# 03_Power.net
KiCad netlist of a schematic drawn in Altium Designer
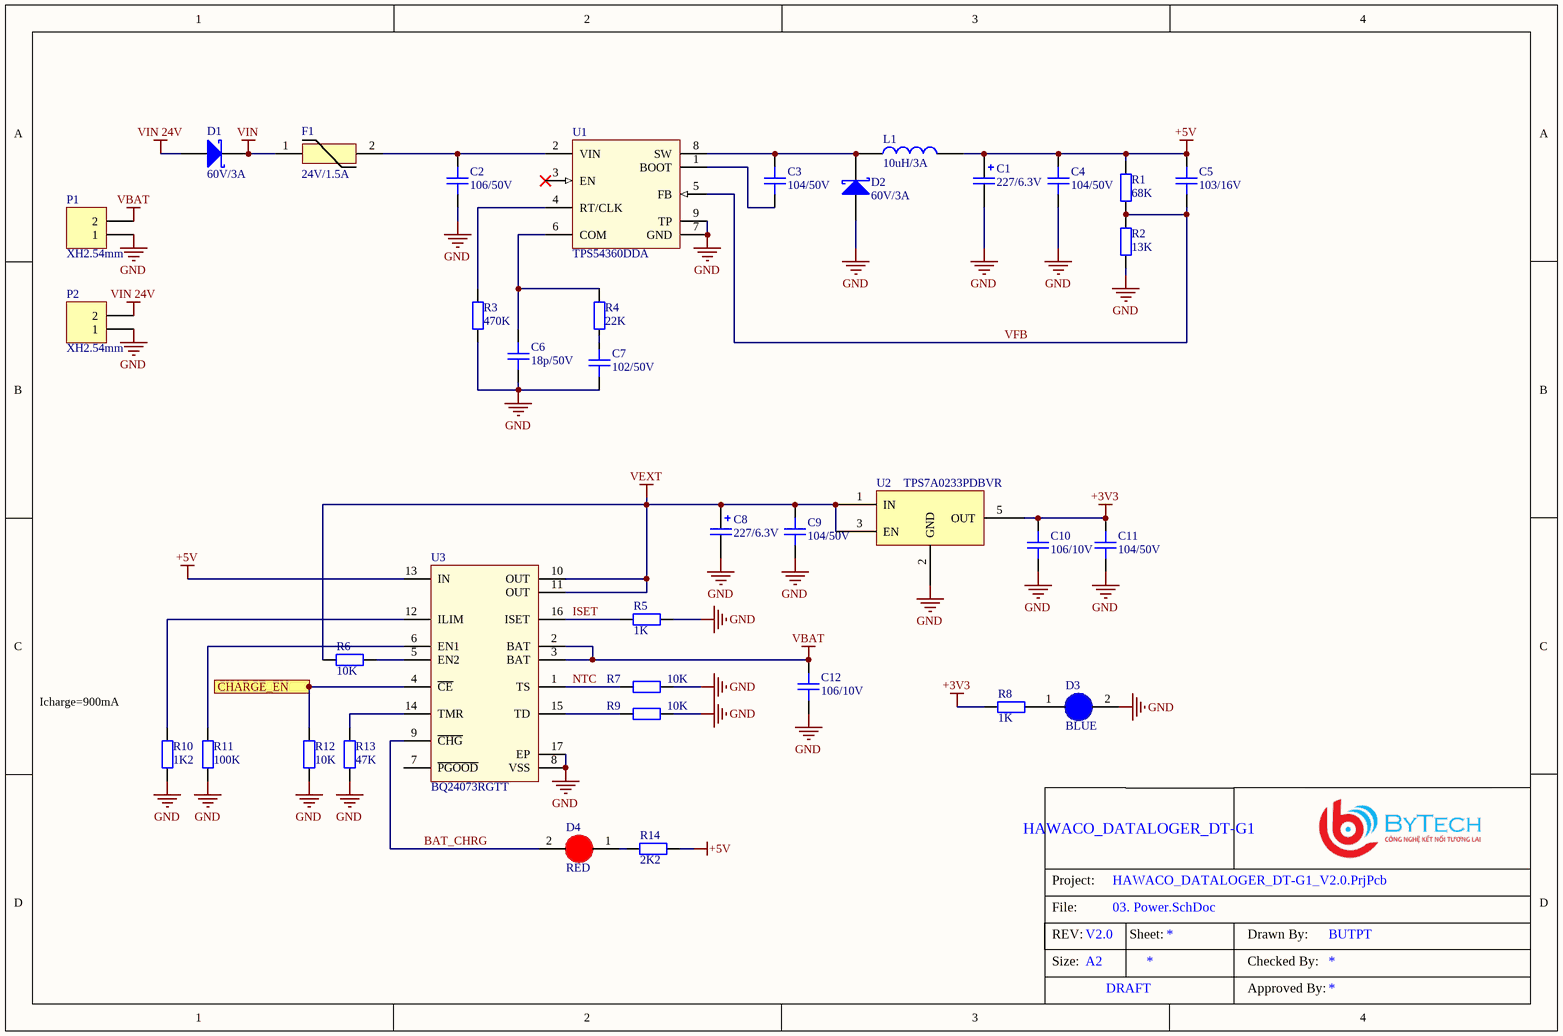
[diagram p0: 03. Power.SchDoc]

(export (version "E")
  (design (tool "Eeschema 10.0.6"))
  (components
    (comp (ref "C1")
      (value "227/6.3V")
      (footprint "CAP_TANTAL_1210(3528)")
      (description "CAP TANT POLY 220uF 20% 6.3V 3528 35mOhm ESR")
      (fields (field (name "MPN") "T520B227M006ATE035"))
      (libsource (lib "01.Passives") (part "T520B227M006ATE035"))
    )
    (comp (ref "C2")
      (value "106/50V")
      (footprint "CAPC-1210 (3225)")
      (description "CAP CER 10uF 10% 50V X7R 1210 (3255)")
      (fields (field (name "MPN") "GRM32ER71H106KA12L"))
      (libsource (lib "01.Passives") (part "GRM32ER71H106KA12L"))
    )
    (comp (ref "C3")
      (value "104/50V")
      (footprint "CAPC-0603 (1608)")
      (description "CAP CER 0.1uF 50V 10% X7R 0603")
      (fields (field (name "MPN") "C0603C104K5RACTU"))
      (libsource (lib "01.Passives") (part "C0603C104K5RACTU"))
    )
    (comp (ref "C4")
      (value "104/50V")
      (footprint "CAPC-0603 (1608)")
      (description "CAP CER 0.1uF 50V 10% X7R 0603")
      (fields (field (name "MPN") "C0603C104K5RACTU"))
      (libsource (lib "01.Passives") (part "C0603C104K5RACTU"))
    )
    (comp (ref "C5")
      (value "103/16V")
      (footprint "CAPC-0603 (1608)")
      (description "CAP CER 10nF 16V 10% X7R 0603")
      (fields (field (name "MPN") "CC0603KRX7R7BB103"))
      (libsource (lib "01.Passives") (part "CC0603KRX7R7BB103"))
    )
    (comp (ref "C6")
      (value "18p/50V")
      (footprint "CAPC-0603 (1608)")
      (description "CAP CER 18pF 5% 50V C0G/NP0 0603")
      (fields (field (name "MPN") "CL10C180JB8NNNC"))
      (libsource (lib "01.Passives") (part "CL10C180JB8NNNC"))
    )
    (comp (ref "C7")
      (value "102/50V")
      (footprint "CAPC-0603 (1608)")
      (description "CAP CER 1nF 50V 10% X7R 0603")
      (fields (field (name "MPN") "C0603C102K5RACTU"))
      (libsource (lib "01.Passives") (part "C0603C102K5RACTU"))
    )
    (comp (ref "C8")
      (value "227/6.3V")
      (footprint "CAP_TANTAL_1210(3528)")
      (description "CAP TANT POLY 220uF 20% 6.3V 3528 35mOhm ESR")
      (fields (field (name "MPN") "T520B227M006ATE035"))
      (libsource (lib "01.Passives") (part "T520B227M006ATE035"))
    )
    (comp (ref "C9")
      (value "104/50V")
      (footprint "CAPC-0603 (1608)")
      (description "CAP CER 0.1uF 50V 10% X7R 0603")
      (fields (field (name "MPN") "C0603C104K5RACTU"))
      (libsource (lib "01.Passives") (part "C0603C104K5RACTU"))
    )
    (comp (ref "C10")
      (value "106/10V")
      (footprint "CAPC-0603 (1608)")
      (description "CAP CER 10uF 10% 10V X5R 0603")
      (fields (field (name "MPN") "CL10A106KP8NNNC"))
      (libsource (lib "01.Passives") (part "CL10A106KP8NNNC"))
    )
    (comp (ref "C11")
      (value "104/50V")
      (footprint "CAPC-0603 (1608)")
      (description "CAP CER 0.1uF 50V 10% X7R 0603")
      (fields (field (name "MPN") "C0603C104K5RACTU"))
      (libsource (lib "01.Passives") (part "C0603C104K5RACTU"))
    )
    (comp (ref "C12")
      (value "106/10V")
      (footprint "CAPC-0603 (1608)")
      (description "CAP CER 10uF 10% 10V X5R 0603")
      (fields (field (name "MPN") "CL10A106KP8NNNC"))
      (libsource (lib "01.Passives") (part "CL10A106KP8NNNC"))
    )
    (comp (ref "D1")
      (value "60V/3A")
      (footprint "DIODE_DO214AC_SMA")
      (description "DIODE SCHOTTKY 60V 3A DO214AC")
      (fields (field (name "MPN") "SK36A-LTP"))
      (libsource (lib "03.Semiconductor") (part "SK36A-LTP"))
    )
    (comp (ref "D2")
      (value "60V/3A")
      (footprint "DIODE_DO214AC_SMA")
      (description "DIODE SCHOTTKY 60V 3A DO214AC")
      (fields (field (name "MPN") "SK36A-LTP") (field (name "MANUFACTURER") "Micro Commercial Co"))
      (libsource (lib "03.Semiconductor") (part "SK36A-LTP"))
    )
    (comp (ref "D3")
      (value "BLUE")
      (footprint "LED 0603")
      (description "LED 0603 BLUE")
      (libsource (lib "03.Semiconductor") (part "LED 0603 BLUE"))
    )
    (comp (ref "D4")
      (value "RED")
      (footprint "LED 0603")
      (description "LED 0603 RED")
      (libsource (lib "03.Semiconductor") (part "LED 0603 RED"))
    )
    (comp (ref "F1")
      (value "24V/1.5A")
      (footprint "FUSE_1812(4532)")
      (description "FUSE PTC RESETTABLE 24V 1.50A 1812L")
      (fields (field (name "MPN") "1812L150/24MR"))
      (libsource (lib "02.Power,Protection") (part "1812L150/24MR"))
    )
    (comp (ref "L1")
      (value "10uH/3A")
      (footprint "IND-IHLP2525-6.86X6.47MM")
      (description "IND-FIXED 10uH 3A 105 mOhm SMD")
      (fields (field (name "MPN") "IHLP2525CZER100M01"))
      (libsource (lib "01.Passives") (part "IHLP2525CZER100M01"))
    )
    (comp (ref "P1")
      (value "XH2.54mm")
      (footprint "XH2.54-2P")
      (description "XH2.54mmm - 2P 180 degree")
      (fields (field (name "MPN") "XH-2A"))
      (libsource (lib "04.Header-Connecter") (part "XH-2A"))
    )
    (comp (ref "P2")
      (value "XH2.54mm")
      (footprint "XH2.54-2P")
      (description "XH2.54mmm - 2P 180 degree")
      (fields (field (name "MPN") "XH-2A"))
      (libsource (lib "04.Header-Connecter") (part "XH-2A"))
    )
    (comp (ref "R1")
      (value "68K")
      (footprint "RESC-0603 (1608)")
      (description "RES SMD 68K OHM 1% 1/10W 0603")
      (fields (field (name "MPN") "CRCW060368K0FKEA"))
      (libsource (lib "01.Passives") (part "CRCW060368K0FKEA"))
    )
    (comp (ref "R2")
      (value "13K")
      (footprint "RESC-0603 (1608)")
      (description "RES SMD 13K OHM 1% 1/10W 0603")
      (fields (field (name "MPN") "AC0603FR-0713KL"))
      (libsource (lib "01.Passives") (part "AC0603FR-0713KL"))
    )
    (comp (ref "R3")
      (value "470K")
      (footprint "RESC-0603 (1608)")
      (description "RES SMD 470K OHM 1% 1/10W 0603")
      (fields (field (name "MPN") "RC0603FR-07470K"))
      (libsource (lib "01.Passives") (part "RC0603FR-07470KL"))
    )
    (comp (ref "R4")
      (value "22K")
      (footprint "RESC-0603 (1608)")
      (description "RES SMD 22K OHM 1% 1/10W 0603")
      (fields (field (name "MPN") "RC0603FR-0722KL"))
      (libsource (lib "01.Passives") (part "RC0603FR-0722KL"))
    )
    (comp (ref "R5")
      (value "1K")
      (footprint "RESC-0603 (1608)")
      (description "RES SMD 1 KOHM 1% 1/10W 0603")
      (fields (field (name "MPN") "RC0603FR-071KL"))
      (libsource (lib "01.Passives") (part "RC0603FR-071KL"))
    )
    (comp (ref "R6")
      (value "10K")
      (footprint "RESC-0603 (1608)")
      (description "RES SMD 10K OHM 1% 1/10W 0603")
      (fields (field (name "MPN") "RC0603FR-0710KL"))
      (libsource (lib "01.Passives") (part "RC0603FR-0710KL"))
    )
    (comp (ref "R7")
      (value "10K")
      (footprint "RESC-0603 (1608)")
      (description "RES SMD 10K OHM 1% 1/10W 0603")
      (fields (field (name "MPN") "RC0603FR-0710KL"))
      (libsource (lib "01.Passives") (part "RC0603FR-0710KL"))
    )
    (comp (ref "R8")
      (value "1K")
      (footprint "RESC-0603 (1608)")
      (description "RES SMD 1 KOHM 1% 1/10W 0603")
      (fields (field (name "MPN") "RC0603FR-071KL"))
      (libsource (lib "01.Passives") (part "RC0603FR-071KL"))
    )
    (comp (ref "R9")
      (value "10K")
      (footprint "RESC-0603 (1608)")
      (description "RES SMD 10K OHM 1% 1/10W 0603")
      (fields (field (name "MPN") "RC0603FR-0710KL"))
      (libsource (lib "01.Passives") (part "RC0603FR-0710KL"))
    )
    (comp (ref "R10")
      (value "1K2")
      (footprint "RESC-0603 (1608)")
      (description "RES SMD 1.2K OHM 1% 1/10W 0603")
      (fields (field (name "MPN") "RC0603FR-071K2L"))
      (libsource (lib "01.Passives") (part "RC0603FR-071K2L"))
    )
    (comp (ref "R11")
      (value "100K")
      (footprint "RESC-0603 (1608)")
      (description "RES SMD 100K OHM 1% 1/10W 0603")
      (fields (field (name "MPN") "RC0603FR-07100KL"))
      (libsource (lib "01.Passives") (part "RC0603FR-07100KL"))
    )
    (comp (ref "R12")
      (value "10K")
      (footprint "RESC-0603 (1608)")
      (description "RES SMD 10K OHM 1% 1/10W 0603")
      (fields (field (name "MPN") "RC0603FR-0710KL"))
      (libsource (lib "") (part "RC0603FR-0710KL_1"))
    )
    (comp (ref "R13")
      (value "47K")
      (footprint "RESC-0603 (1608)")
      (description "RES SMD 47K OHM 1% 1/10W 0603")
      (fields (field (name "MPN") "RC0603FR0747KL"))
      (libsource (lib "01.Passives") (part "RC0603FR0747KL"))
    )
    (comp (ref "R14")
      (value "2K2")
      (footprint "RESC-0603 (1608)")
      (description "RES SMD 2.2K OHM 1% 1/10W 0603")
      (fields (field (name "MPN") "CRCW06032K20FKEA"))
      (libsource (lib "01.Passives") (part "CRCW06032K20FKEA"))
    )
    (comp (ref "U1")
      (value "TPS54360DDA")
      (footprint "DDA8_3P1X2P4")
      (description "IC REG BCK SPLIT RAIL ADJ 8SOPWR")
      (fields (field (name "MANUFACTURER") "Texas Instruments"))
      (libsource (lib "05.IC") (part "TPS54360DDA"))
    )
    (comp (ref "U2")
      (value "TPS7A0233PDBVR")
      (footprint "SOT23-5")
      (description "NANOPOWER LDO")
      (libsource (lib "05.IC") (part "TPS7A0233PDBVR"))
    )
    (comp (ref "U3")
      (value "BQ24073RGTT")
      (footprint "RGT16-1700X1700TP")
      (description "IC LI-ION CHARGE/PWR MGMT 16-QFN")
      (fields (field (name "MFR") "Texas Instruments"))
      (libsource (lib "05.IC") (part "BQ24073RGTT"))
    )
  )
  (nets
    (net (code "1") (name "+3V3") (class "Default")
      (node (ref "C10") (pin "2") (pinfunction "2_2") (pintype "passive"))
      (node (ref "C11") (pin "2") (pinfunction "2_2") (pintype "passive"))
      (node (ref "R8") (pin "1") (pinfunction "1_1") (pintype "passive"))
      (node (ref "U2") (pin "5") (pinfunction "OUT_5") (pintype "passive"))
    )
    (net (code "2") (name "+5V") (class "Default")
      (node (ref "C1") (pin "1") (pinfunction "1_1") (pintype "passive"))
      (node (ref "C4") (pin "2") (pinfunction "2_2") (pintype "passive"))
      (node (ref "C5") (pin "2") (pinfunction "2_2") (pintype "passive"))
      (node (ref "L1") (pin "2") (pinfunction "2_2") (pintype "passive"))
      (node (ref "R1") (pin "2") (pinfunction "2_2") (pintype "passive"))
      (node (ref "R14") (pin "2") (pinfunction "2_2") (pintype "passive"))
      (node (ref "U3") (pin "13") (pinfunction "IN_13") (pintype "power_in"))
    )
    (net (code "3") (name "/BAT_CHRG") (class "Default")
      (node (ref "D4") (pin "2") (pinfunction "K_2") (pintype "passive"))
      (node (ref "U3") (pin "9") (pinfunction "~{CHG}_9") (pintype "power_in"))
    )
    (net (code "4") (name "/CHARGE_EN") (class "Default")
      (node (ref "R12") (pin "2") (pinfunction "2_2") (pintype "passive"))
      (node (ref "U3") (pin "4") (pinfunction "~{CE}_4") (pintype "passive"))
    )
    (net (code "5") (name "/ISET") (class "Default")
      (node (ref "R5") (pin "1") (pinfunction "1_1") (pintype "passive"))
      (node (ref "U3") (pin "16") (pinfunction "ISET_16") (pintype "power_in"))
    )
    (net (code "6") (name "/NTC") (class "Default")
      (node (ref "R7") (pin "1") (pinfunction "1_1") (pintype "passive"))
      (node (ref "U3") (pin "1") (pinfunction "TS_1") (pintype "power_in"))
    )
    (net (code "7") (name "/VFB") (class "Default")
      (node (ref "C5") (pin "1") (pinfunction "1_1") (pintype "passive"))
      (node (ref "R1") (pin "1") (pinfunction "1_1") (pintype "passive"))
      (node (ref "R2") (pin "2") (pinfunction "2_2") (pintype "passive"))
      (node (ref "U1") (pin "5") (pinfunction "FB_5") (pintype "input"))
    )
    (net (code "8") (name "GND") (class "Default")
      (node (ref "C1") (pin "2") (pinfunction "2_2") (pintype "passive"))
      (node (ref "C10") (pin "1") (pinfunction "1_1") (pintype "passive"))
      (node (ref "C11") (pin "1") (pinfunction "1_1") (pintype "passive"))
      (node (ref "C12") (pin "1") (pinfunction "1_1") (pintype "passive"))
      (node (ref "C2") (pin "1") (pinfunction "1_1") (pintype "passive"))
      (node (ref "C4") (pin "1") (pinfunction "1_1") (pintype "passive"))
      (node (ref "C6") (pin "1") (pinfunction "1_1") (pintype "passive"))
      (node (ref "C7") (pin "1") (pinfunction "1_1") (pintype "passive"))
      (node (ref "C8") (pin "2") (pinfunction "2_2") (pintype "passive"))
      (node (ref "C9") (pin "1") (pinfunction "1_1") (pintype "passive"))
      (node (ref "D2") (pin "1") (pinfunction "A_1") (pintype "passive"))
      (node (ref "D3") (pin "2") (pinfunction "K_2") (pintype "passive"))
      (node (ref "P1") (pin "1") (pinfunction "1_1") (pintype "passive"))
      (node (ref "P2") (pin "1") (pinfunction "1_1") (pintype "passive"))
      (node (ref "R10") (pin "1") (pinfunction "1_1") (pintype "passive"))
      (node (ref "R11") (pin "1") (pinfunction "1_1") (pintype "passive"))
      (node (ref "R12") (pin "1") (pinfunction "1_1") (pintype "passive"))
      (node (ref "R13") (pin "1") (pinfunction "1_1") (pintype "passive"))
      (node (ref "R2") (pin "1") (pinfunction "1_1") (pintype "passive"))
      (node (ref "R3") (pin "1") (pinfunction "1_1") (pintype "passive"))
      (node (ref "R5") (pin "2") (pinfunction "2_2") (pintype "passive"))
      (node (ref "R7") (pin "2") (pinfunction "2_2") (pintype "passive"))
      (node (ref "R9") (pin "2") (pinfunction "2_2") (pintype "passive"))
      (node (ref "U1") (pin "7") (pinfunction "GND_7") (pintype "passive"))
      (node (ref "U1") (pin "9") (pinfunction "TP_9") (pintype "passive"))
      (node (ref "U2") (pin "2") (pinfunction "GND_2") (pintype "passive"))
      (node (ref "U3") (pin "17") (pinfunction "EP_17") (pintype "power_in"))
      (node (ref "U3") (pin "8") (pinfunction "VSS_8") (pintype "power_in"))
    )
    (net (code "9") (name "Net-(C7-Pad2)") (class "Default")
      (node (ref "C7") (pin "2") (pinfunction "2_2") (pintype "passive"))
      (node (ref "R4") (pin "1") (pinfunction "1_1") (pintype "passive"))
    )
    (net (code "10") (name "Net-(D2-K)") (class "Default")
      (node (ref "C3") (pin "1") (pinfunction "1_1") (pintype "passive"))
      (node (ref "D2") (pin "2") (pinfunction "K_2") (pintype "passive"))
      (node (ref "L1") (pin "1") (pinfunction "1_1") (pintype "passive"))
      (node (ref "U1") (pin "8") (pinfunction "SW_8") (pintype "passive"))
    )
    (net (code "11") (name "Net-(D3-A)") (class "Default")
      (node (ref "D3") (pin "1") (pinfunction "A_1") (pintype "passive"))
      (node (ref "R8") (pin "2") (pinfunction "2_2") (pintype "passive"))
    )
    (net (code "12") (name "Net-(D4-A)") (class "Default")
      (node (ref "D4") (pin "1") (pinfunction "A_1") (pintype "passive"))
      (node (ref "R14") (pin "1") (pinfunction "1_1") (pintype "passive"))
    )
    (net (code "13") (name "Net-(U1-BOOT)") (class "Default")
      (node (ref "C3") (pin "2") (pinfunction "2_2") (pintype "passive"))
      (node (ref "U1") (pin "1") (pinfunction "BOOT_1") (pintype "passive"))
    )
    (net (code "14") (name "Net-(U1-COM)") (class "Default")
      (node (ref "C6") (pin "2") (pinfunction "2_2") (pintype "passive"))
      (node (ref "R4") (pin "2") (pinfunction "2_2") (pintype "passive"))
      (node (ref "U1") (pin "6") (pinfunction "COM_6") (pintype "passive"))
    )
    (net (code "15") (name "Net-(U1-RT{slash}CLK)") (class "Default")
      (node (ref "R3") (pin "2") (pinfunction "2_2") (pintype "passive"))
      (node (ref "U1") (pin "4") (pinfunction "RT/CLK_4") (pintype "passive"))
    )
    (net (code "16") (name "Net-(U1-VIN)") (class "Default")
      (node (ref "C2") (pin "2") (pinfunction "2_2") (pintype "passive"))
      (node (ref "F1") (pin "2") (pinfunction "2_2") (pintype "passive"))
      (node (ref "U1") (pin "2") (pinfunction "VIN_2") (pintype "passive"))
    )
    (net (code "17") (name "Net-(U3-EN1)") (class "Default")
      (node (ref "R11") (pin "2") (pinfunction "2_2") (pintype "passive"))
      (node (ref "U3") (pin "6") (pinfunction "EN1_6") (pintype "power_in"))
    )
    (net (code "18") (name "Net-(U3-EN2)") (class "Default")
      (node (ref "R6") (pin "2") (pinfunction "2_2") (pintype "passive"))
      (node (ref "U3") (pin "5") (pinfunction "EN2_5") (pintype "power_in"))
    )
    (net (code "19") (name "Net-(U3-ILIM)") (class "Default")
      (node (ref "R10") (pin "2") (pinfunction "2_2") (pintype "passive"))
      (node (ref "U3") (pin "12") (pinfunction "ILIM_12") (pintype "power_in"))
    )
    (net (code "20") (name "Net-(U3-TD)") (class "Default")
      (node (ref "R9") (pin "1") (pinfunction "1_1") (pintype "passive"))
      (node (ref "U3") (pin "15") (pinfunction "TD_15") (pintype "power_in"))
    )
    (net (code "21") (name "Net-(U3-TMR)") (class "Default")
      (node (ref "R13") (pin "2") (pinfunction "2_2") (pintype "passive"))
      (node (ref "U3") (pin "14") (pinfunction "TMR_14") (pintype "power_in"))
    )
    (net (code "22") (name "VBAT") (class "Default")
      (node (ref "C12") (pin "2") (pinfunction "2_2") (pintype "passive"))
      (node (ref "P1") (pin "2") (pinfunction "2_2") (pintype "passive"))
      (node (ref "U3") (pin "2") (pinfunction "BAT_2") (pintype "power_in"))
      (node (ref "U3") (pin "3") (pinfunction "BAT_3") (pintype "power_in"))
    )
    (net (code "23") (name "VEXT") (class "Default")
      (node (ref "C8") (pin "1") (pinfunction "1_1") (pintype "passive"))
      (node (ref "C9") (pin "2") (pinfunction "2_2") (pintype "passive"))
      (node (ref "R6") (pin "1") (pinfunction "1_1") (pintype "passive"))
      (node (ref "U2") (pin "1") (pinfunction "IN_1") (pintype "passive"))
      (node (ref "U2") (pin "3") (pinfunction "EN_3") (pintype "passive"))
      (node (ref "U3") (pin "10") (pinfunction "OUT_10") (pintype "power_in"))
      (node (ref "U3") (pin "11") (pinfunction "OUT_11") (pintype "power_in"))
    )
    (net (code "24") (name "VIN") (class "Default")
      (node (ref "D1") (pin "2") (pinfunction "K_2") (pintype "passive"))
      (node (ref "F1") (pin "1") (pinfunction "1_1") (pintype "passive"))
    )
    (net (code "25") (name "VIN 24V") (class "Default")
      (node (ref "D1") (pin "1") (pinfunction "A_1") (pintype "passive"))
      (node (ref "P2") (pin "2") (pinfunction "2_2") (pintype "passive"))
    )
    (net (code "26") (name "unconnected-(U1-EN-Pad3)") (class "Default")
      (node (ref "U1") (pin "3") (pinfunction "EN_3") (pintype "input+no_connect"))
    )
    (net (code "27") (name "unconnected-(U3-~{PGOOD}-Pad7)") (class "Default")
      (node (ref "U3") (pin "7") (pinfunction "~{PGOOD}_7") (pintype "power_in"))
    )
  )
)
